# schematic_001.net
KiCad netlist of a schematic drawn in EAGLE
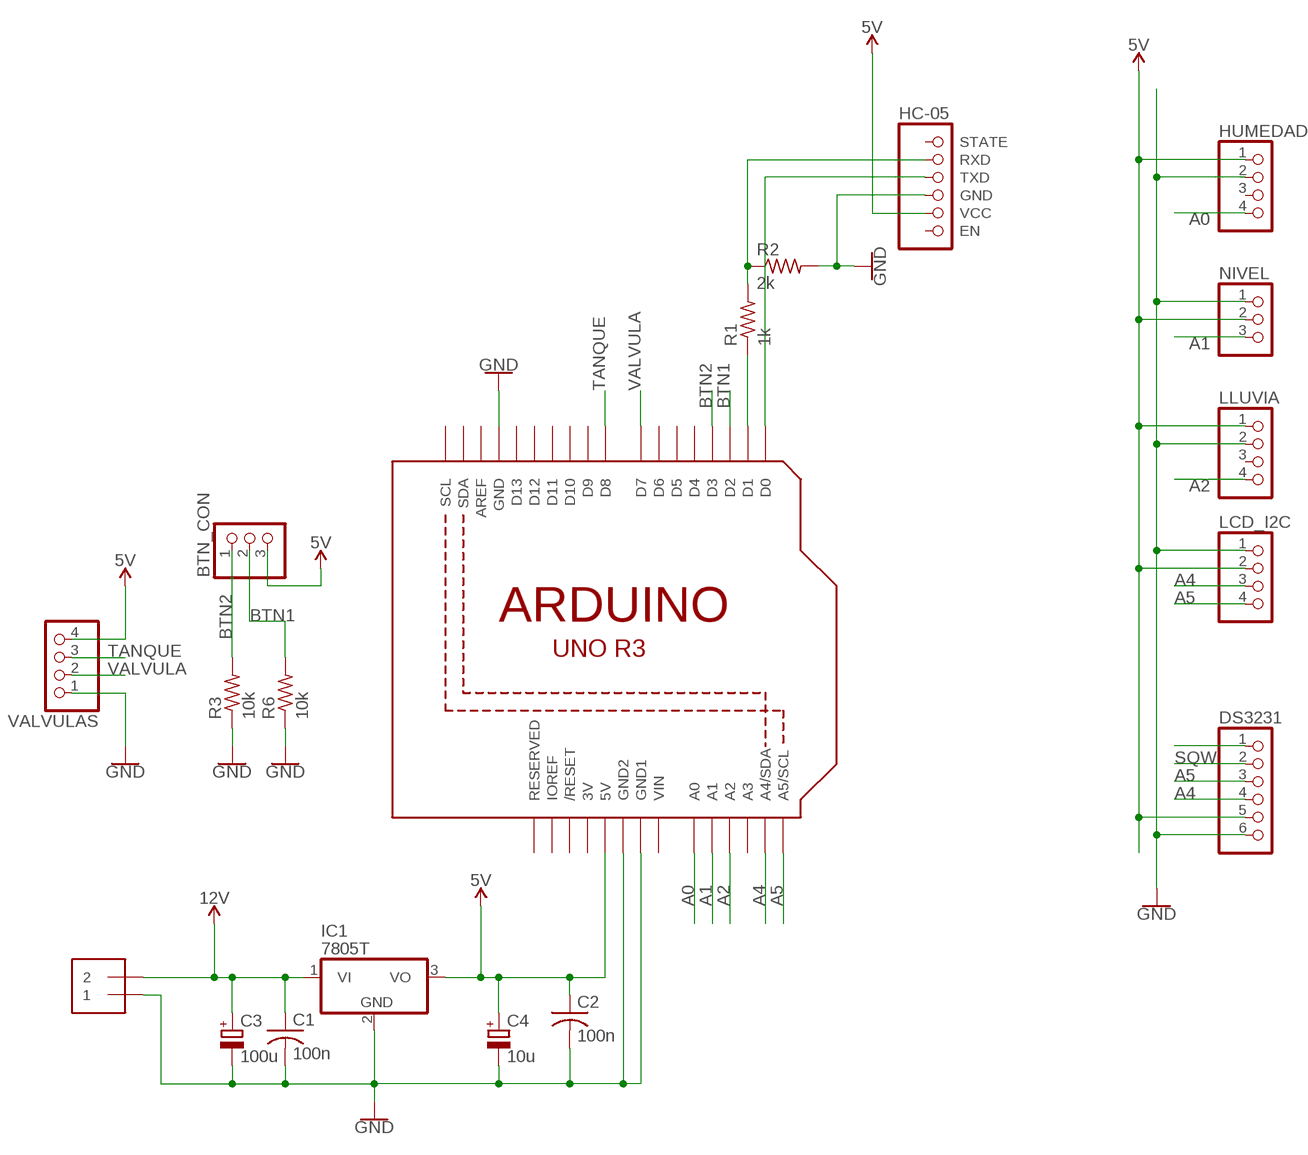
[diagram p0: schematic, sheet 1]

(export (version "E")
  (design (tool "Eeschema 10.0.6"))
  (components
    (comp (ref "BTN_CON")
      (value "PINHD-1X3")
      (footprint "eagle-import:1X03")
      (libsource (lib "eagle-import") (part "PINHD-1X3"))
    )
    (comp (ref "C1")
      (value "100n")
      (footprint "eagle-import:C050-024X044")
      (libsource (lib "eagle-import") (part "C-US050-024X044"))
    )
    (comp (ref "C2")
      (value "100n")
      (footprint "eagle-import:C050-024X044")
      (libsource (lib "eagle-import") (part "C-US050-024X044"))
    )
    (comp (ref "C3")
      (value "100u")
      (footprint "eagle-import:E2,5-7")
      (libsource (lib "eagle-import") (part "CPOL-EUE2.5-7"))
    )
    (comp (ref "C4")
      (value "10u")
      (footprint "eagle-import:E2,5-7")
      (libsource (lib "eagle-import") (part "CPOL-EUE2.5-7"))
    )
    (comp (ref "DS3231")
      (value "PINHD-1X6")
      (footprint "eagle-import:1X06")
      (libsource (lib "eagle-import") (part "PINHD-1X6"))
    )
    (comp (ref "HC-05")
      (value "HC-05")
      (footprint "eagle-import:1X06")
      (libsource (lib "eagle-import") (part "HC-05"))
    )
    (comp (ref "HUMEDAD")
      (value "PINHD-1X4")
      (footprint "eagle-import:1X04")
      (libsource (lib "eagle-import") (part "PINHD-1X4"))
    )
    (comp (ref "IC1")
      (value "7805T")
      (footprint "eagle-import:TO220H")
      (libsource (lib "eagle-import") (part "78T05"))
    )
    (comp (ref "J1")
      (value "1X2-3.5MM")
      (footprint "eagle-import:1X2-3.5MM")
      (libsource (lib "eagle-import") (part "1X2-3.5MM"))
    )
    (comp (ref "LCD_I2C")
      (value "PINHD-1X4")
      (footprint "eagle-import:1X04")
      (libsource (lib "eagle-import") (part "PINHD-1X4"))
    )
    (comp (ref "LLUVIA")
      (value "PINHD-1X4")
      (footprint "eagle-import:1X04")
      (libsource (lib "eagle-import") (part "PINHD-1X4"))
    )
    (comp (ref "NIVEL")
      (value "PINHD-1X3")
      (footprint "eagle-import:1X03")
      (libsource (lib "eagle-import") (part "PINHD-1X3"))
    )
    (comp (ref "R1")
      (value "1k")
      (footprint "eagle-import:0204_7")
      (libsource (lib "eagle-import") (part "R-US_0204/7"))
    )
    (comp (ref "R2")
      (value "2k")
      (footprint "eagle-import:0204_7")
      (libsource (lib "eagle-import") (part "R-US_0204/7"))
    )
    (comp (ref "R3")
      (value "10k")
      (footprint "eagle-import:0204_7")
      (libsource (lib "eagle-import") (part "R-US_0204/7"))
    )
    (comp (ref "R6")
      (value "10k")
      (footprint "eagle-import:0204_7")
      (libsource (lib "eagle-import") (part "R-US_0204/7"))
    )
    (comp (ref "U1")
      (value "ARDUINOR3-BPLACE")
      (footprint "eagle-import:ARDUINOR3-BPLACE")
      (libsource (lib "eagle-import") (part "ARDUINOR3-BPLACE"))
    )
    (comp (ref "VALVULAS")
      (value "PINHD-1X4")
      (footprint "eagle-import:1X04")
      (libsource (lib "eagle-import") (part "PINHD-1X4"))
    )
  )
  (nets
    (net (code "1") (name "/3V") (class "Default")
      (node (ref "U1") (pin "3V") (pinfunction "3V_3V") (pintype "power_in"))
    )
    (net (code "2") (name "/A0") (class "Default")
      (node (ref "HUMEDAD") (pin "4") (pinfunction "4_4") (pintype "passive"))
      (node (ref "U1") (pin "A0") (pinfunction "A0_A0") (pintype "bidirectional"))
    )
    (net (code "3") (name "/A1") (class "Default")
      (node (ref "NIVEL") (pin "3") (pinfunction "3_3") (pintype "passive"))
      (node (ref "U1") (pin "A1") (pinfunction "A1_A1") (pintype "bidirectional"))
    )
    (net (code "4") (name "/A2") (class "Default")
      (node (ref "LLUVIA") (pin "4") (pinfunction "4_4") (pintype "passive"))
      (node (ref "U1") (pin "A2") (pinfunction "A2_A2") (pintype "bidirectional"))
    )
    (net (code "5") (name "/A4") (class "Default")
      (node (ref "DS3231") (pin "4") (pinfunction "4_4") (pintype "passive"))
      (node (ref "LCD_I2C") (pin "3") (pinfunction "3_3") (pintype "passive"))
      (node (ref "U1") (pin "A4") (pinfunction "A4/SDA_A4") (pintype "bidirectional"))
    )
    (net (code "6") (name "/A5") (class "Default")
      (node (ref "DS3231") (pin "3") (pinfunction "3_3") (pintype "passive"))
      (node (ref "LCD_I2C") (pin "4") (pinfunction "4_4") (pintype "passive"))
      (node (ref "U1") (pin "A5") (pinfunction "A5/SCL_A5") (pintype "bidirectional"))
    )
    (net (code "7") (name "/BTN1") (class "Default")
      (node (ref "BTN_CON") (pin "2") (pinfunction "2_2") (pintype "passive"))
      (node (ref "R6") (pin "2") (pinfunction "2_2") (pintype "passive"))
      (node (ref "U1") (pin "D2") (pinfunction "D2_D2") (pintype "bidirectional"))
    )
    (net (code "8") (name "/BTN2") (class "Default")
      (node (ref "BTN_CON") (pin "1") (pinfunction "1_1") (pintype "passive"))
      (node (ref "R3") (pin "2") (pinfunction "2_2") (pintype "passive"))
      (node (ref "U1") (pin "D3") (pinfunction "D3_D3") (pintype "bidirectional"))
    )
    (net (code "9") (name "/SQW") (class "Default")
      (node (ref "DS3231") (pin "2") (pinfunction "2_2") (pintype "passive"))
    )
    (net (code "10") (name "/TANQUE") (class "Default")
      (node (ref "U1") (pin "D8") (pinfunction "D8_D8") (pintype "bidirectional"))
      (node (ref "VALVULAS") (pin "3") (pinfunction "3_3") (pintype "passive"))
    )
    (net (code "11") (name "/VALVULA") (class "Default")
      (node (ref "U1") (pin "D7") (pinfunction "D7_D7") (pintype "bidirectional"))
      (node (ref "VALVULAS") (pin "2") (pinfunction "2_2") (pintype "passive"))
    )
    (net (code "12") (name "/VIN") (class "Default")
      (node (ref "U1") (pin "VIN") (pinfunction "VIN_VIN") (pintype "power_in"))
    )
    (net (code "13") (name "5V") (class "Default")
      (node (ref "BTN_CON") (pin "3") (pinfunction "3_3") (pintype "passive"))
      (node (ref "C2") (pin "1") (pinfunction "1_1") (pintype "passive"))
      (node (ref "C4") (pin "+") (pinfunction "+_+") (pintype "passive"))
      (node (ref "DS3231") (pin "5") (pinfunction "5_5") (pintype "passive"))
      (node (ref "HC-05") (pin "5") (pinfunction "VCC_5") (pintype "power_in"))
      (node (ref "HUMEDAD") (pin "1") (pinfunction "1_1") (pintype "passive"))
      (node (ref "IC1") (pin "3") (pinfunction "VO_3") (pintype "passive"))
      (node (ref "LCD_I2C") (pin "2") (pinfunction "2_2") (pintype "passive"))
      (node (ref "LLUVIA") (pin "1") (pinfunction "1_1") (pintype "passive"))
      (node (ref "NIVEL") (pin "2") (pinfunction "2_2") (pintype "passive"))
      (node (ref "U1") (pin "5V") (pinfunction "5V_5V") (pintype "power_in"))
      (node (ref "VALVULAS") (pin "4") (pinfunction "4_4") (pintype "passive"))
    )
    (net (code "14") (name "12V") (class "Default")
      (node (ref "C1") (pin "1") (pinfunction "1_1") (pintype "passive"))
      (node (ref "C3") (pin "+") (pinfunction "+_+") (pintype "passive"))
      (node (ref "IC1") (pin "1") (pinfunction "VI_1") (pintype "input"))
      (node (ref "J1") (pin "2") (pinfunction "2_2") (pintype "passive"))
    )
    (net (code "15") (name "GND") (class "Default")
      (node (ref "C1") (pin "2") (pinfunction "2_2") (pintype "passive"))
      (node (ref "C2") (pin "2") (pinfunction "2_2") (pintype "passive"))
      (node (ref "C3") (pin "-") (pinfunction "-_-") (pintype "passive"))
      (node (ref "C4") (pin "-") (pinfunction "-_-") (pintype "passive"))
      (node (ref "DS3231") (pin "6") (pinfunction "6_6") (pintype "passive"))
      (node (ref "HC-05") (pin "4") (pinfunction "GND_4") (pintype "power_in"))
      (node (ref "HUMEDAD") (pin "2") (pinfunction "2_2") (pintype "passive"))
      (node (ref "IC1") (pin "2") (pinfunction "GND_2") (pintype "passive"))
      (node (ref "J1") (pin "1") (pinfunction "1_1") (pintype "passive"))
      (node (ref "LCD_I2C") (pin "1") (pinfunction "1_1") (pintype "passive"))
      (node (ref "LLUVIA") (pin "2") (pinfunction "2_2") (pintype "passive"))
      (node (ref "NIVEL") (pin "1") (pinfunction "1_1") (pintype "passive"))
      (node (ref "R2") (pin "2") (pinfunction "2_2") (pintype "passive"))
      (node (ref "R3") (pin "1") (pinfunction "1_1") (pintype "passive"))
      (node (ref "R6") (pin "1") (pinfunction "1_1") (pintype "passive"))
      (node (ref "U1") (pin "GND") (pinfunction "GND_GND") (pintype "power_in"))
      (node (ref "U1") (pin "GND1") (pinfunction "GND1_GND1") (pintype "power_in"))
      (node (ref "U1") (pin "GND2") (pinfunction "GND2_GND2") (pintype "power_in"))
      (node (ref "VALVULAS") (pin "1") (pinfunction "1_1") (pintype "passive"))
    )
    (net (code "16") (name "Net-(HC-05-RXD)") (class "Default")
      (node (ref "HC-05") (pin "2") (pinfunction "RXD_2") (pintype "input"))
      (node (ref "R1") (pin "2") (pinfunction "2_2") (pintype "passive"))
      (node (ref "R2") (pin "1") (pinfunction "1_1") (pintype "passive"))
    )
    (net (code "17") (name "Net-(HC-05-TXD)") (class "Default")
      (node (ref "HC-05") (pin "3") (pinfunction "TXD_3") (pintype "output"))
      (node (ref "U1") (pin "D0") (pinfunction "D0_D0") (pintype "bidirectional"))
    )
    (net (code "18") (name "Net-(R1-Pad1)") (class "Default")
      (node (ref "R1") (pin "1") (pinfunction "1_1") (pintype "passive"))
      (node (ref "U1") (pin "D1") (pinfunction "D1_D1") (pintype "bidirectional"))
    )
    (net (code "19") (name "unconnected-(DS3231-Pad1)") (class "Default")
      (node (ref "DS3231") (pin "1") (pinfunction "1_1") (pintype "passive"))
    )
    (net (code "20") (name "unconnected-(HC-05-EN-Pad6)") (class "Default")
      (node (ref "HC-05") (pin "6") (pinfunction "EN_6") (pintype "input"))
    )
    (net (code "21") (name "unconnected-(HC-05-STATE-Pad1)") (class "Default")
      (node (ref "HC-05") (pin "1") (pinfunction "STATE_1") (pintype "output"))
    )
    (net (code "22") (name "unconnected-(HUMEDAD-Pad3)") (class "Default")
      (node (ref "HUMEDAD") (pin "3") (pinfunction "3_3") (pintype "passive"))
    )
    (net (code "23") (name "unconnected-(LLUVIA-Pad3)") (class "Default")
      (node (ref "LLUVIA") (pin "3") (pinfunction "3_3") (pintype "passive"))
    )
    (net (code "24") (name "unconnected-(U1-PadA3)") (class "Default")
      (node (ref "U1") (pin "A3") (pinfunction "A3_A3") (pintype "bidirectional"))
    )
    (net (code "25") (name "unconnected-(U1-PadAREF)") (class "Default")
      (node (ref "U1") (pin "AREF") (pinfunction "AREF_AREF") (pintype "bidirectional"))
    )
    (net (code "26") (name "unconnected-(U1-PadD4)") (class "Default")
      (node (ref "U1") (pin "D4") (pinfunction "D4_D4") (pintype "bidirectional"))
    )
    (net (code "27") (name "unconnected-(U1-PadD5)") (class "Default")
      (node (ref "U1") (pin "D5") (pinfunction "D5_D5") (pintype "bidirectional"))
    )
    (net (code "28") (name "unconnected-(U1-PadD6)") (class "Default")
      (node (ref "U1") (pin "D6") (pinfunction "D6_D6") (pintype "bidirectional"))
    )
    (net (code "29") (name "unconnected-(U1-PadD9)") (class "Default")
      (node (ref "U1") (pin "D9") (pinfunction "D9_D9") (pintype "bidirectional"))
    )
    (net (code "30") (name "unconnected-(U1-PadD10)") (class "Default")
      (node (ref "U1") (pin "D10") (pinfunction "D10_D10") (pintype "bidirectional"))
    )
    (net (code "31") (name "unconnected-(U1-PadD11)") (class "Default")
      (node (ref "U1") (pin "D11") (pinfunction "D11_D11") (pintype "bidirectional"))
    )
    (net (code "32") (name "unconnected-(U1-PadD12)") (class "Default")
      (node (ref "U1") (pin "D12") (pinfunction "D12_D12") (pintype "bidirectional"))
    )
    (net (code "33") (name "unconnected-(U1-PadD13)") (class "Default")
      (node (ref "U1") (pin "D13") (pinfunction "D13_D13") (pintype "bidirectional"))
    )
    (net (code "34") (name "unconnected-(U1-PadIOREF)") (class "Default")
      (node (ref "U1") (pin "IOREF") (pinfunction "IOREF_IOREF") (pintype "output"))
    )
    (net (code "35") (name "unconnected-(U1-PadRESERVED)") (class "Default")
      (node (ref "U1") (pin "RESERVED") (pinfunction "RESERVED_RESERVED") (pintype "no_connect"))
    )
    (net (code "36") (name "unconnected-(U1-PadSCL)") (class "Default")
      (node (ref "U1") (pin "SCL") (pinfunction "SCL_SCL") (pintype "bidirectional"))
    )
    (net (code "37") (name "unconnected-(U1-PadSDA)") (class "Default")
      (node (ref "U1") (pin "SDA") (pinfunction "SDA_SDA") (pintype "bidirectional"))
    )
    (net (code "38") (name "unconnected-(U1-{slash}RESET-PadRESET)") (class "Default")
      (node (ref "U1") (pin "RESET") (pinfunction "/RESET_RESET") (pintype "bidirectional"))
    )
  )
)
